# BMS_ERROR_Detection.net
KiCad netlist of a schematic drawn in Altium Designer
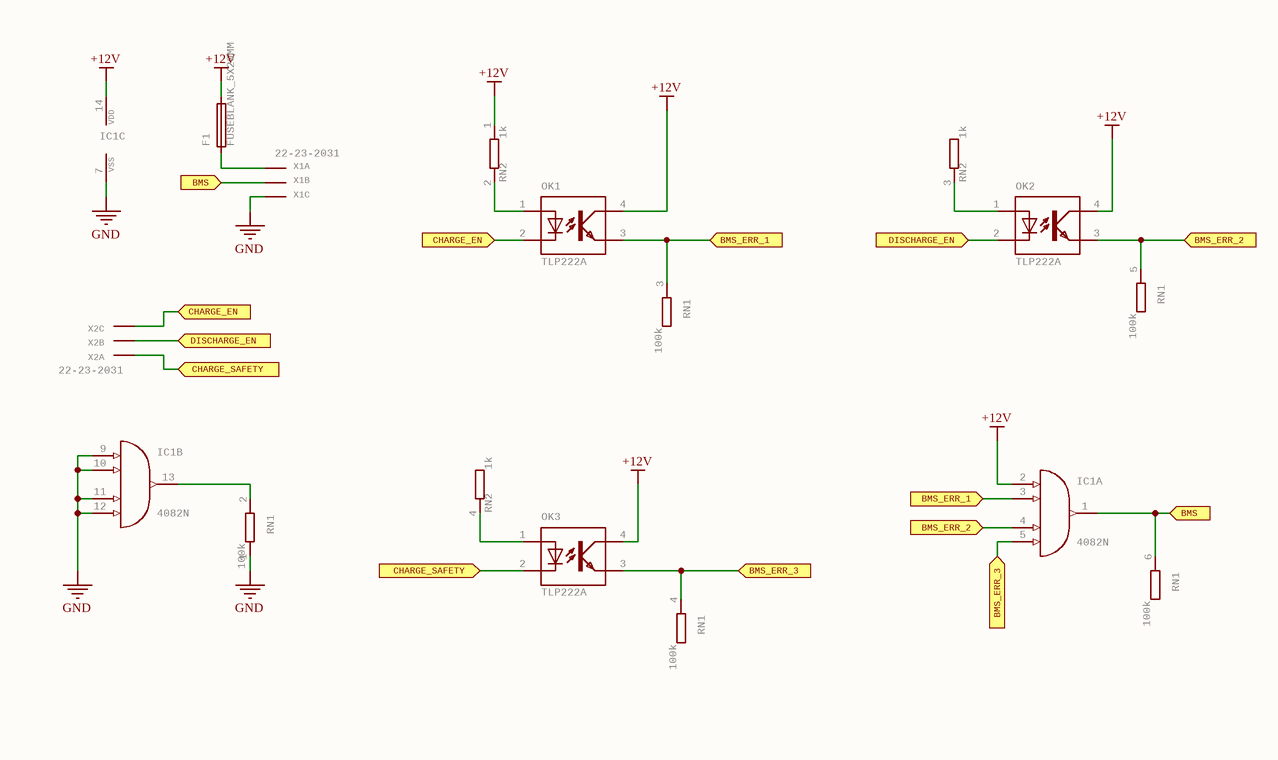
[diagram p0: BMS ERROR Detection.SchDoc]

(export (version "E")
  (design (tool "Eeschema 10.0.6"))
  (components
    (comp (ref "F1")
      (value "FUSEBLANK_5X20MM")
      (footprint "FUSE_HOLDER_5X20MM")
      (description "Fuse")
      (fields (field (name "MF") "MF") (field (name "MPN") "MPN"))
      (libsource (lib "fuse") (part "FUSEBLANK_5X20MM"))
    )
    (comp (ref "IC1")
      (value "4082N")
      (footprint "DIL14")
      (description "Dual 4-input AND")
      (fields (field (name "VDD") "VDD") (field (name "VSS") "VSS"))
      (libsource (lib "40xx") (part "4082N"))
    )
    (comp (ref "OK1")
      (value "TLP222A")
      (footprint "DIL04")
      (description "OPTO COUPLER   Source: LITEON, LTV816.pdf")
      (fields (field (name "MF") "MF") (field (name "MPN") "MPN"))
      (libsource (lib "optocoupler") (part "LTV816"))
    )
    (comp (ref "OK2")
      (value "TLP222A")
      (footprint "DIL04")
      (description "OPTO COUPLER   Source: LITEON, LTV816.pdf")
      (fields (field (name "MF") "MF") (field (name "MPN") "MPN"))
      (libsource (lib "optocoupler") (part "LTV816"))
    )
    (comp (ref "OK3")
      (value "TLP222A")
      (footprint "DIL04")
      (description "OPTO COUPLER   Source: LITEON, LTV816.pdf")
      (fields (field (name "MF") "MF") (field (name "MPN") "MPN"))
      (libsource (lib "optocoupler") (part "LTV816"))
    )
    (comp (ref "RN1")
      (value "100k")
      (footprint "SIL6")
      (description "SIL RESISTOR")
      (fields (field (name "PART") "RN1") (field (name "MF") "MF") (field (name "MPN") "MPN"))
      (libsource (lib "resistor-sil") (part "GE05RP"))
    )
    (comp (ref "RN2")
      (value "1k")
      (footprint "SIL4")
      (description "SIL RESISTOR")
      (fields (field (name "PART") "RN2") (field (name "MF") "MF") (field (name "MPN") "MPN"))
      (libsource (lib "resistor-sil") (part "GE03RP"))
    )
    (comp (ref "X1")
      (value "22-23-2031")
      (footprint "22-23-2031")
      (description ".100\" (2.54mm) Center Header - 3 Pin")
      (fields (field (name "MF") "MOLEX"))
      (libsource (lib "con-molex") (part "22-23-2031"))
    )
    (comp (ref "X2")
      (value "22-23-2031")
      (footprint "22-23-2031")
      (description ".100\" (2.54mm) Center Header - 3 Pin")
      (fields (field (name "MF") "MOLEX"))
      (libsource (lib "con-molex") (part "22-23-2031"))
    )
  )
  (nets
    (net (code "1") (name "+12V") (class "Default")
      (node (ref "F1") (pin "2") (pinfunction "2_2") (pintype "passive"))
      (node (ref "IC1") (pin "14") (pinfunction "VDD_14") (pintype "power_in"))
      (node (ref "IC1") (pin "2") (pinfunction "I0_2") (pintype "input"))
      (node (ref "OK1") (pin "4") (pinfunction "COL_4") (pintype "passive"))
      (node (ref "OK2") (pin "4") (pinfunction "COL_4") (pintype "passive"))
      (node (ref "OK3") (pin "4") (pinfunction "COL_4") (pintype "passive"))
      (node (ref "RN2") (pin "1") (pinfunction "1_1") (pintype "passive"))
    )
    (net (code "2") (name "/BMS") (class "Default")
      (node (ref "IC1") (pin "1") (pinfunction "O_1") (pintype "output"))
      (node (ref "RN1") (pin "6") (pinfunction "2_6") (pintype "passive"))
      (node (ref "X1") (pin "2") (pinfunction "S_2") (pintype "passive"))
    )
    (net (code "3") (name "/BMS_ERR_1") (class "Default")
      (node (ref "IC1") (pin "3") (pinfunction "I1_3") (pintype "input"))
      (node (ref "OK1") (pin "3") (pinfunction "EMIT_3") (pintype "passive"))
      (node (ref "RN1") (pin "3") (pinfunction "2_3") (pintype "passive"))
    )
    (net (code "4") (name "/BMS_ERR_2") (class "Default")
      (node (ref "IC1") (pin "4") (pinfunction "I2_4") (pintype "input"))
      (node (ref "OK2") (pin "3") (pinfunction "EMIT_3") (pintype "passive"))
      (node (ref "RN1") (pin "5") (pinfunction "2_5") (pintype "passive"))
    )
    (net (code "5") (name "/BMS_ERR_3") (class "Default")
      (node (ref "IC1") (pin "5") (pinfunction "I3_5") (pintype "input"))
      (node (ref "OK3") (pin "3") (pinfunction "EMIT_3") (pintype "passive"))
      (node (ref "RN1") (pin "4") (pinfunction "2_4") (pintype "passive"))
    )
    (net (code "6") (name "/CHARGE_EN") (class "Default")
      (node (ref "OK1") (pin "2") (pinfunction "C_2") (pintype "passive"))
      (node (ref "X2") (pin "3") (pinfunction "S_3") (pintype "passive"))
    )
    (net (code "7") (name "/CHARGE_SAFETY") (class "Default")
      (node (ref "OK3") (pin "2") (pinfunction "C_2") (pintype "passive"))
      (node (ref "X2") (pin "1") (pinfunction "S_1") (pintype "passive"))
    )
    (net (code "8") (name "/DISCHARGE_EN") (class "Default")
      (node (ref "OK2") (pin "2") (pinfunction "C_2") (pintype "passive"))
      (node (ref "X2") (pin "2") (pinfunction "S_2") (pintype "passive"))
    )
    (net (code "9") (name "GND") (class "Default")
      (node (ref "IC1") (pin "10") (pinfunction "I1_10") (pintype "input"))
      (node (ref "IC1") (pin "11") (pinfunction "I2_11") (pintype "input"))
      (node (ref "IC1") (pin "12") (pinfunction "I3_12") (pintype "input"))
      (node (ref "IC1") (pin "7") (pinfunction "VSS_7") (pintype "power_in"))
      (node (ref "IC1") (pin "9") (pinfunction "I0_9") (pintype "input"))
      (node (ref "RN1") (pin "1") (pinfunction "1_1") (pintype "passive"))
      (node (ref "X1") (pin "3") (pinfunction "S_3") (pintype "passive"))
    )
    (net (code "10") (name "Net-(IC1B-O)") (class "Default")
      (node (ref "IC1") (pin "13") (pinfunction "O_13") (pintype "output"))
      (node (ref "RN1") (pin "2") (pinfunction "2_2") (pintype "passive"))
    )
    (net (code "11") (name "Net-(OK1-A)") (class "Default")
      (node (ref "OK1") (pin "1") (pinfunction "A_1") (pintype "passive"))
      (node (ref "RN2") (pin "2") (pinfunction "2_2") (pintype "passive"))
    )
    (net (code "12") (name "Net-(OK2-A)") (class "Default")
      (node (ref "OK2") (pin "1") (pinfunction "A_1") (pintype "passive"))
      (node (ref "RN2") (pin "3") (pinfunction "2_3") (pintype "passive"))
    )
    (net (code "13") (name "Net-(OK3-A)") (class "Default")
      (node (ref "OK3") (pin "1") (pinfunction "A_1") (pintype "passive"))
      (node (ref "RN2") (pin "4") (pinfunction "2_4") (pintype "passive"))
    )
    (net (code "14") (name "Net-(X1A-S)") (class "Default")
      (node (ref "F1") (pin "1") (pinfunction "1_1") (pintype "passive"))
      (node (ref "X1") (pin "1") (pinfunction "S_1") (pintype "passive"))
    )
  )
)
